# Salinity.net
KiCad netlist of a schematic drawn in Altium Designer
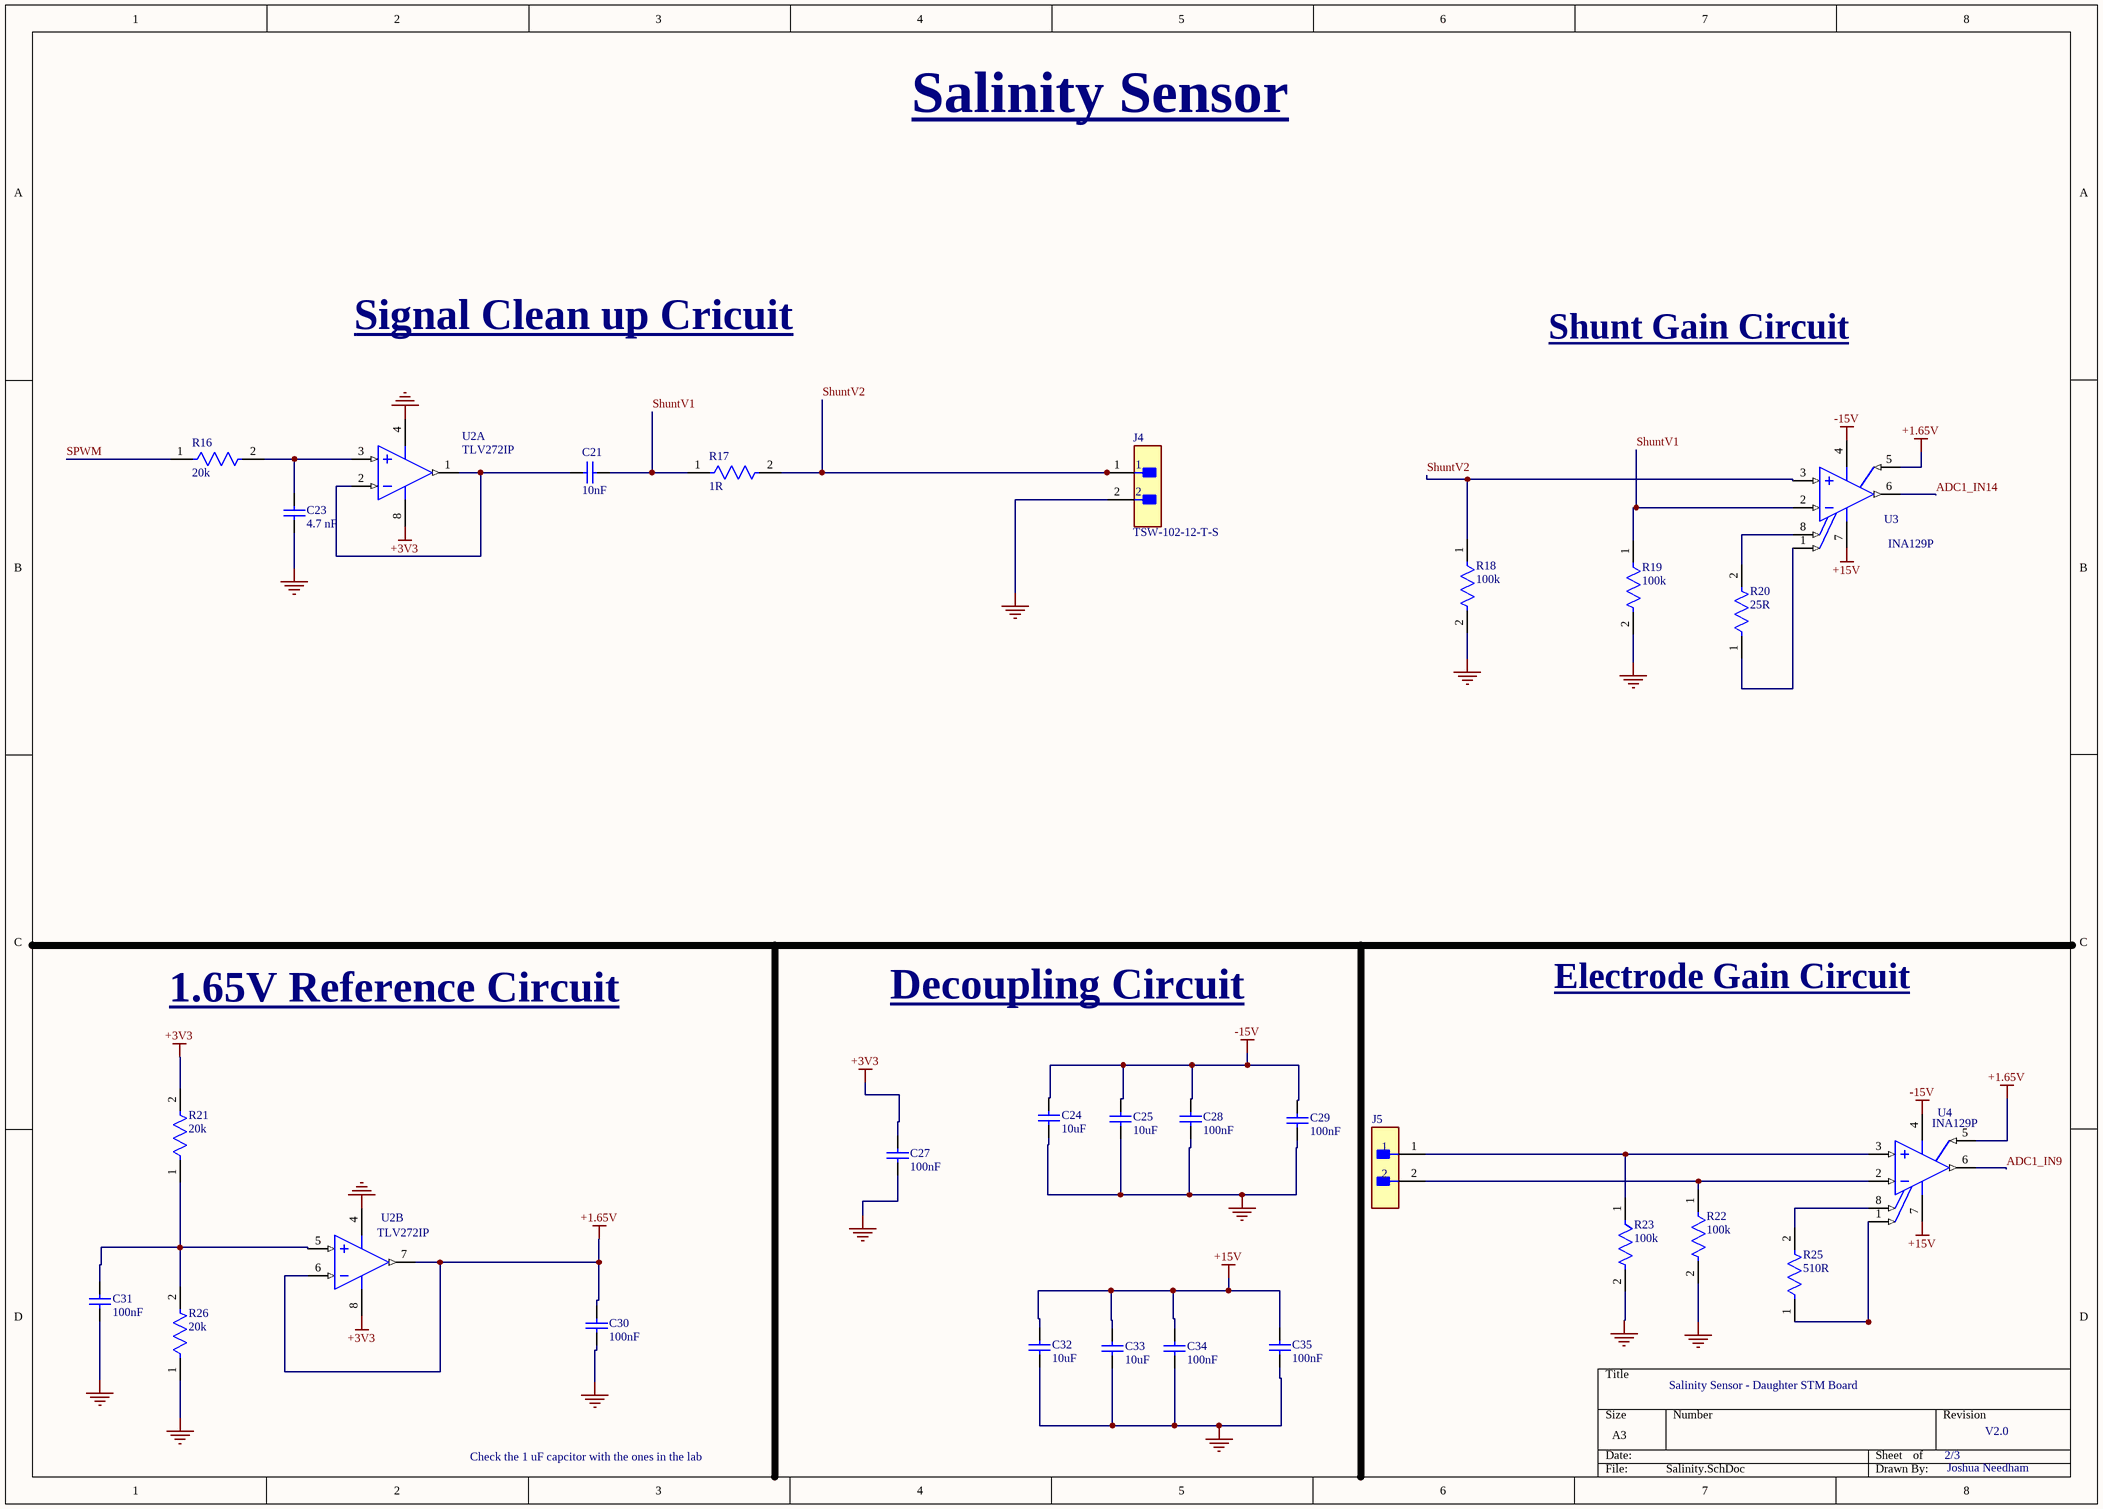
[diagram p0: Salinity.SchDoc]

(export (version "E")
  (design (tool "Eeschema 10.0.6"))
  (components
    (comp (ref "C21")
      (value "10nF")
      (footprint "CAPC0805(2012)100_M")
      (description "CAP 100nF 10V ±5% 0805 (2012 Metric) Thickness 1mm SMD")
      (fields (field (name "TOLERANCE") "Â±5%"))
      (libsource (lib "Altium Content Vault") (part "CAP"))
    )
    (comp (ref "C23")
      (value "4.7 nF")
      (footprint "CAPC0805(2012)100_M")
      (description "CAP 100nF 10V ±5% 0805 (2012 Metric) Thickness 1mm SMD")
      (fields (field (name "TOLERANCE") "Â±5%"))
      (libsource (lib "Altium Content Vault") (part "CAP"))
    )
    (comp (ref "C24")
      (value "10uF")
      (footprint "CAPC0805(2012)100_M")
      (description "CAP 100nF 10V ±5% 0805 (2012 Metric) Thickness 1mm SMD")
      (fields (field (name "TOLERANCE") "Â±5%"))
      (libsource (lib "Altium Content Vault") (part "CAP"))
    )
    (comp (ref "C25")
      (value "10uF")
      (footprint "CAPC0805(2012)100_M")
      (description "CAP 100nF 10V ±5% 0805 (2012 Metric) Thickness 1mm SMD")
      (fields (field (name "TOLERANCE") "Â±5%"))
      (libsource (lib "Altium Content Vault") (part "CAP"))
    )
    (comp (ref "C27")
      (value "100nF")
      (footprint "CAPC0805(2012)100_M")
      (description "CAP 100nF 10V ±5% 0805 (2012 Metric) Thickness 1mm SMD")
      (fields (field (name "TOLERANCE") "Â±5%"))
      (libsource (lib "Altium Content Vault") (part "CAP"))
    )
    (comp (ref "C28")
      (value "100nF")
      (footprint "CAPC0805(2012)100_M")
      (description "CAP 100nF 10V ±5% 0805 (2012 Metric) Thickness 1mm SMD")
      (fields (field (name "TOLERANCE") "Â±5%"))
      (libsource (lib "Altium Content Vault") (part "CAP"))
    )
    (comp (ref "C29")
      (value "100nF")
      (footprint "CAPC0805(2012)100_M")
      (description "CAP 100nF 10V ±5% 0805 (2012 Metric) Thickness 1mm SMD")
      (fields (field (name "TOLERANCE") "Â±5%"))
      (libsource (lib "Altium Content Vault") (part "CAP"))
    )
    (comp (ref "C30")
      (value "100nF")
      (footprint "CAPC0805(2012)100_M")
      (description "CAP 100nF 10V ±5% 0805 (2012 Metric) Thickness 1mm SMD")
      (fields (field (name "TOLERANCE") "Â±5%"))
      (libsource (lib "Altium Content Vault") (part "CAP"))
    )
    (comp (ref "C31")
      (value "100nF")
      (footprint "CAPC0805(2012)100_M")
      (description "CAP 100nF 10V ±5% 0805 (2012 Metric) Thickness 1mm SMD")
      (fields (field (name "TOLERANCE") "Â±5%"))
      (libsource (lib "Altium Content Vault") (part "CAP"))
    )
    (comp (ref "C32")
      (value "10uF")
      (footprint "CAPC0805(2012)100_M")
      (description "CAP 100nF 10V ±5% 0805 (2012 Metric) Thickness 1mm SMD")
      (fields (field (name "TOLERANCE") "Â±5%"))
      (libsource (lib "Altium Content Vault") (part "CAP"))
    )
    (comp (ref "C33")
      (value "10uF")
      (footprint "CAPC0805(2012)100_M")
      (description "CAP 100nF 10V ±5% 0805 (2012 Metric) Thickness 1mm SMD")
      (fields (field (name "TOLERANCE") "Â±5%"))
      (libsource (lib "Altium Content Vault") (part "CAP"))
    )
    (comp (ref "C34")
      (value "100nF")
      (footprint "CAPC0805(2012)100_M")
      (description "CAP 100nF 10V ±5% 0805 (2012 Metric) Thickness 1mm SMD")
      (fields (field (name "TOLERANCE") "Â±5%"))
      (libsource (lib "Altium Content Vault") (part "CAP"))
    )
    (comp (ref "C35")
      (value "100nF")
      (footprint "CAPC0805(2012)100_M")
      (description "CAP 100nF 10V ±5% 0805 (2012 Metric) Thickness 1mm SMD")
      (fields (field (name "TOLERANCE") "Â±5%"))
      (libsource (lib "Altium Content Vault") (part "CAP"))
    )
    (comp (ref "J4")
      (value "TSW-102-12-T-S")
      (footprint "FP-TSW-102-12-T-S-MFG")
      (description "CONN HEADER VERT 2POS 2.54MM")
      (libsource (lib "") (part "3bc925449376181038e59eaffc5286c_1"))
    )
    (comp (ref "J5")
      (value "TSW-102-12-T-S")
      (footprint "FP-TSW-102-12-T-S-MFG")
      (description "CONN HEADER VERT 2POS 2.54MM")
      (libsource (lib "Altium Content Vault") (part "3bc925449376181038e59eaffc5286c"))
    )
    (comp (ref "R16")
      (value "20k")
      (footprint "FP-CRCW0805-e3-IPC_A")
      (description "RES Thick Film, 680Ω, 5%, 0.125W, 200ppm/°C, 0805")
      (fields (field (name "TOLERANCE") "5%"))
      (libsource (lib "Altium Content Vault") (part "1029c3af85768c4190bb7ad29bc67b5"))
    )
    (comp (ref "R17")
      (value "1R")
      (footprint "FP-CRCW0805-e3-IPC_A")
      (description "RES Thick Film, 680Ω, 5%, 0.125W, 200ppm/°C, 0805")
      (fields (field (name "TOLERANCE") "5%"))
      (libsource (lib "Altium Content Vault") (part "1029c3af85768c4190bb7ad29bc67b5"))
    )
    (comp (ref "R18")
      (value "100k")
      (footprint "FP-CRCW0805-e3-IPC_A")
      (description "RES Thick Film, 680Ω, 5%, 0.125W, 200ppm/°C, 0805")
      (fields (field (name "TOLERANCE") "5%"))
      (libsource (lib "Altium Content Vault") (part "1029c3af85768c4190bb7ad29bc67b5"))
    )
    (comp (ref "R19")
      (value "100k")
      (footprint "FP-CRCW0805-e3-IPC_A")
      (description "RES Thick Film, 680Ω, 5%, 0.125W, 200ppm/°C, 0805")
      (fields (field (name "TOLERANCE") "5%"))
      (libsource (lib "Altium Content Vault") (part "1029c3af85768c4190bb7ad29bc67b5"))
    )
    (comp (ref "R20")
      (value "25R")
      (footprint "FP-CRCW0805-e3-IPC_A")
      (description "RES Thick Film, 680Ω, 5%, 0.125W, 200ppm/°C, 0805")
      (fields (field (name "TOLERANCE") "5%"))
      (libsource (lib "Altium Content Vault") (part "1029c3af85768c4190bb7ad29bc67b5"))
    )
    (comp (ref "R21")
      (value "20k")
      (footprint "FP-CRCW0805-e3-IPC_A")
      (description "RES Thick Film, 680Ω, 5%, 0.125W, 200ppm/°C, 0805")
      (fields (field (name "TOLERANCE") "5%"))
      (libsource (lib "Altium Content Vault") (part "1029c3af85768c4190bb7ad29bc67b5"))
    )
    (comp (ref "R22")
      (value "100k")
      (footprint "FP-CRCW0805-e3-IPC_A")
      (description "RES Thick Film, 680Ω, 5%, 0.125W, 200ppm/°C, 0805")
      (fields (field (name "TOLERANCE") "5%"))
      (libsource (lib "Altium Content Vault") (part "1029c3af85768c4190bb7ad29bc67b5"))
    )
    (comp (ref "R23")
      (value "100k")
      (footprint "FP-CRCW0805-e3-IPC_A")
      (description "RES Thick Film, 680Ω, 5%, 0.125W, 200ppm/°C, 0805")
      (fields (field (name "TOLERANCE") "5%"))
      (libsource (lib "Altium Content Vault") (part "1029c3af85768c4190bb7ad29bc67b5"))
    )
    (comp (ref "R25")
      (value "510R")
      (footprint "FP-CRCW0805-e3-IPC_A")
      (description "RES Thick Film, 680Ω, 5%, 0.125W, 200ppm/°C, 0805")
      (fields (field (name "TOLERANCE") "5%"))
      (libsource (lib "Altium Content Vault") (part "1029c3af85768c4190bb7ad29bc67b5"))
    )
    (comp (ref "R26")
      (value "20k")
      (footprint "FP-CRCW0805-e3-IPC_A")
      (description "RES Thick Film, 680Ω, 5%, 0.125W, 200ppm/°C, 0805")
      (fields (field (name "TOLERANCE") "5%"))
      (libsource (lib "Altium Content Vault") (part "1029c3af85768c4190bb7ad29bc67b5"))
    )
    (comp (ref "U2")
      (value "TLV272IP")
      (footprint "P0008A")
      (fields (field (name "MANUFACTURER") "Texas Instruments"))
      (libsource (lib "Altium Content Vault") (part "TI-TLV_TLC-8"))
    )
    (comp (ref "U3")
      (value "INA129P")
      (footprint "P0008A")
      (fields (field (name "MANUFACTURER") "Texas Instruments"))
      (libsource (lib "Altium Content Vault") (part "TI-INA1XX-8"))
    )
    (comp (ref "U4")
      (value "INA129P")
      (footprint "P0008A")
      (fields (field (name "MANUFACTURER") "Texas Instruments"))
      (libsource (lib "Altium Content Vault") (part "TI-INA1XX-8"))
    )
  )
  (nets
    (net (code "1") (name "+1.65V") (class "Default")
      (node (ref "C30") (pin "2") (pinfunction "2_2") (pintype "passive"))
      (node (ref "U2") (pin "6") (pinfunction "IN2-_6") (pintype "input"))
      (node (ref "U2") (pin "7") (pinfunction "OUT2_7") (pintype "output"))
      (node (ref "U3") (pin "5") (pinfunction "REF_5") (pintype "input"))
      (node (ref "U4") (pin "5") (pinfunction "REF_5") (pintype "input"))
    )
    (net (code "2") (name "+3V3") (class "Default")
      (node (ref "C27") (pin "2") (pinfunction "2_2") (pintype "passive"))
      (node (ref "R21") (pin "2") (pinfunction "2_2") (pintype "passive"))
      (node (ref "U2") (pin "8") (pinfunction "VDD_8") (pintype "power_in"))
    )
    (net (code "3") (name "+15V") (class "Default")
      (node (ref "C32") (pin "2") (pinfunction "2_2") (pintype "passive"))
      (node (ref "C33") (pin "2") (pinfunction "2_2") (pintype "passive"))
      (node (ref "C34") (pin "2") (pinfunction "2_2") (pintype "passive"))
      (node (ref "C35") (pin "2") (pinfunction "2_2") (pintype "passive"))
      (node (ref "U3") (pin "7") (pinfunction "V+_7") (pintype "power_in"))
      (node (ref "U4") (pin "7") (pinfunction "V+_7") (pintype "power_in"))
    )
    (net (code "4") (name "-15V") (class "Default")
      (node (ref "C24") (pin "2") (pinfunction "2_2") (pintype "passive"))
      (node (ref "C25") (pin "2") (pinfunction "2_2") (pintype "passive"))
      (node (ref "C28") (pin "2") (pinfunction "2_2") (pintype "passive"))
      (node (ref "C29") (pin "2") (pinfunction "2_2") (pintype "passive"))
      (node (ref "U3") (pin "4") (pinfunction "V-_4") (pintype "power_in"))
      (node (ref "U4") (pin "4") (pinfunction "V-_4") (pintype "power_in"))
    )
    (net (code "5") (name "/ADC1_IN9") (class "Default")
      (node (ref "U4") (pin "6") (pinfunction "VO_6") (pintype "output"))
    )
    (net (code "6") (name "/ADC1_IN14") (class "Default")
      (node (ref "U3") (pin "6") (pinfunction "VO_6") (pintype "output"))
    )
    (net (code "7") (name "/SPWM") (class "Default")
      (node (ref "R16") (pin "1") (pinfunction "1_1") (pintype "passive"))
    )
    (net (code "8") (name "/ShuntV1") (class "Default")
      (node (ref "C21") (pin "1") (pinfunction "1_1") (pintype "passive"))
      (node (ref "R17") (pin "1") (pinfunction "1_1") (pintype "passive"))
      (node (ref "R19") (pin "1") (pinfunction "1_1") (pintype "passive"))
      (node (ref "U3") (pin "2") (pinfunction "VIN-_2") (pintype "input"))
    )
    (net (code "9") (name "/ShuntV2") (class "Default")
      (node (ref "J4") (pin "1") (pinfunction "1_1") (pintype "passive"))
      (node (ref "R17") (pin "2") (pinfunction "2_2") (pintype "passive"))
      (node (ref "R18") (pin "1") (pinfunction "1_1") (pintype "passive"))
      (node (ref "U3") (pin "3") (pinfunction "VIN+_3") (pintype "input"))
    )
    (net (code "10") (name "GND") (class "Default")
      (node (ref "C23") (pin "1") (pinfunction "1_1") (pintype "passive"))
      (node (ref "C24") (pin "1") (pinfunction "1_1") (pintype "passive"))
      (node (ref "C25") (pin "1") (pinfunction "1_1") (pintype "passive"))
      (node (ref "C27") (pin "1") (pinfunction "1_1") (pintype "passive"))
      (node (ref "C28") (pin "1") (pinfunction "1_1") (pintype "passive"))
      (node (ref "C29") (pin "1") (pinfunction "1_1") (pintype "passive"))
      (node (ref "C30") (pin "1") (pinfunction "1_1") (pintype "passive"))
      (node (ref "C31") (pin "1") (pinfunction "1_1") (pintype "passive"))
      (node (ref "C32") (pin "1") (pinfunction "1_1") (pintype "passive"))
      (node (ref "C33") (pin "1") (pinfunction "1_1") (pintype "passive"))
      (node (ref "C34") (pin "1") (pinfunction "1_1") (pintype "passive"))
      (node (ref "C35") (pin "1") (pinfunction "1_1") (pintype "passive"))
      (node (ref "J4") (pin "2") (pinfunction "2_2") (pintype "passive"))
      (node (ref "R18") (pin "2") (pinfunction "2_2") (pintype "passive"))
      (node (ref "R19") (pin "2") (pinfunction "2_2") (pintype "passive"))
      (node (ref "R22") (pin "2") (pinfunction "2_2") (pintype "passive"))
      (node (ref "R23") (pin "2") (pinfunction "2_2") (pintype "passive"))
      (node (ref "R26") (pin "1") (pinfunction "1_1") (pintype "passive"))
      (node (ref "U2") (pin "4") (pinfunction "GND_4") (pintype "power_in"))
    )
    (net (code "11") (name "Net-(R20-Pad1)") (class "Default")
      (node (ref "R20") (pin "1") (pinfunction "1_1") (pintype "passive"))
      (node (ref "U3") (pin "1") (pinfunction "RG_1") (pintype "input"))
    )
    (net (code "12") (name "Net-(R20-Pad2)") (class "Default")
      (node (ref "R20") (pin "2") (pinfunction "2_2") (pintype "passive"))
      (node (ref "U3") (pin "8") (pinfunction "RG_8") (pintype "input"))
    )
    (net (code "13") (name "Net-(R25-Pad1)") (class "Default")
      (node (ref "R25") (pin "1") (pinfunction "1_1") (pintype "passive"))
      (node (ref "U4") (pin "1") (pinfunction "RG_1") (pintype "input"))
    )
    (net (code "14") (name "Net-(R25-Pad2)") (class "Default")
      (node (ref "R25") (pin "2") (pinfunction "2_2") (pintype "passive"))
      (node (ref "U4") (pin "8") (pinfunction "RG_8") (pintype "input"))
    )
    (net (code "15") (name "Net-(U2A-IN1+)") (class "Default")
      (node (ref "C23") (pin "2") (pinfunction "2_2") (pintype "passive"))
      (node (ref "R16") (pin "2") (pinfunction "2_2") (pintype "passive"))
      (node (ref "U2") (pin "3") (pinfunction "IN1+_3") (pintype "input"))
    )
    (net (code "16") (name "Net-(U2A-IN1-)") (class "Default")
      (node (ref "C21") (pin "2") (pinfunction "2_2") (pintype "passive"))
      (node (ref "U2") (pin "1") (pinfunction "OUT1_1") (pintype "output"))
      (node (ref "U2") (pin "2") (pinfunction "IN1-_2") (pintype "input"))
    )
    (net (code "17") (name "Net-(U2B-IN2+)") (class "Default")
      (node (ref "C31") (pin "2") (pinfunction "2_2") (pintype "passive"))
      (node (ref "R21") (pin "1") (pinfunction "1_1") (pintype "passive"))
      (node (ref "R26") (pin "2") (pinfunction "2_2") (pintype "passive"))
      (node (ref "U2") (pin "5") (pinfunction "IN2+_5") (pintype "input"))
    )
    (net (code "18") (name "Net-(U4-VIN+)") (class "Default")
      (node (ref "J5") (pin "1") (pinfunction "1_1") (pintype "passive"))
      (node (ref "R23") (pin "1") (pinfunction "1_1") (pintype "passive"))
      (node (ref "U4") (pin "3") (pinfunction "VIN+_3") (pintype "input"))
    )
    (net (code "19") (name "Net-(U4-VIN-)") (class "Default")
      (node (ref "J5") (pin "2") (pinfunction "2_2") (pintype "passive"))
      (node (ref "R22") (pin "1") (pinfunction "1_1") (pintype "passive"))
      (node (ref "U4") (pin "2") (pinfunction "VIN-_2") (pintype "input"))
    )
  )
)
